# Sheet1.net
KiCad netlist of a schematic drawn in Altium Designer
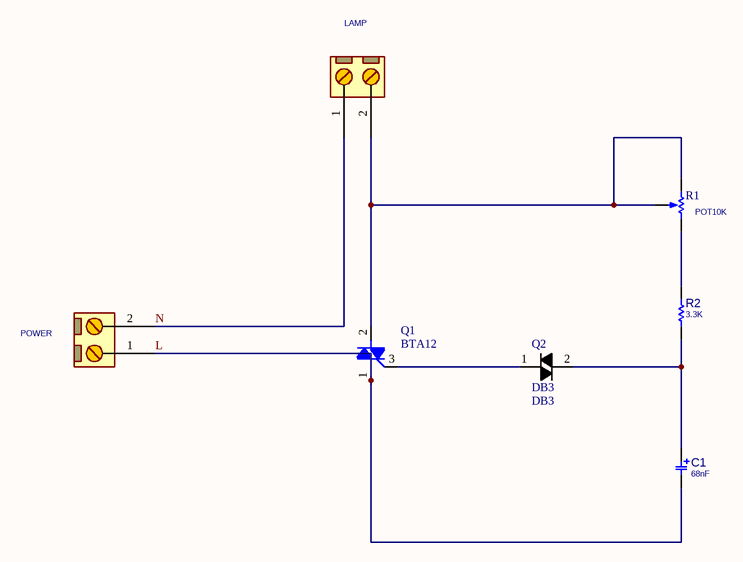
[diagram p0: Sheet1.SchDoc]

(export (version "E")
  (design (tool "Eeschema 10.0.6"))
  (components
    (comp (ref "C1")
      (value "68nF")
      (footprint "C_FLM_7X5H11")
      (description "CAP, THD, FILM,")
      (fields (field (name "MANF_P#") "MANF_PART#") (field (name "MANF") "MANF"))
      (libsource (lib "passive_thd") (part "CAP_THD_FLM"))
    )
    (comp (ref "LAMP")
      (value "CONN_TB2")
      (footprint "MSTB_2")
      (description "CONN, PHOENIX MSTB, 5-G, 5.08mm pitch")
      (libsource (lib "") (part "CONN_MSTB_2_1"))
    )
    (comp (ref "POWER")
      (value "CONN_TB2")
      (footprint "MSTB_2")
      (description "CONN, PHOENIX MSTB, 5-G, 5.08mm pitch")
      (libsource (lib "conn_terminalB") (part "CONN_MSTB_2"))
    )
    (comp (ref "Q1")
      (value "BTA12")
      (footprint "TO220_3")
      (description "Triac, 600V, 12A, TO-220")
      (fields (field (name "MANF_P#") "BTA12-600BW, BTA12-600CW, BTA12-600TW") (field (name "MANF") "ST"))
      (libsource (lib "triac_diac") (part "TRIAC_BTA12-600_TO220"))
    )
    (comp (ref "Q2")
      (value "DB3")
      (footprint "D_AX03_DO35")
      (description "Diac, 32VBO, DO-35")
      (fields (field (name "MANF") "ST") (field (name "ALTIUM_VALUE") "DB3"))
      (libsource (lib "triac_diac") (part "DIAC_DB3_DO35"))
    )
    (comp (ref "R1")
      (value "POT10K")
      (footprint "VOL_R")
      (description "RESISTOR, THD, Potentiometer Volume")
      (libsource (lib "resistor_pot_trimmer") (part "RES_THD_POT_VOL"))
    )
    (comp (ref "R2")
      (value "3.3K")
      (footprint "R025W_AX04")
      (description "RESISTOR, THD")
      (fields (field (name "MANF_P#") "RK73H1ETTP4701F") (field (name "MANF") "KOA SPEER"))
      (libsource (lib "passive_thd") (part "RES_THD"))
    )
  )
  (nets
    (net (code "1") (name "/L") (class "Default")
      (node (ref "C1") (pin "2") (pinfunction "2_2") (pintype "passive"))
      (node (ref "POWER") (pin "1") (pinfunction "1_1") (pintype "passive"))
      (node (ref "Q1") (pin "1") (pinfunction "T1_1") (pintype "passive"))
    )
    (net (code "2") (name "/N") (class "Default")
      (node (ref "LAMP") (pin "1") (pinfunction "1_1") (pintype "passive"))
      (node (ref "POWER") (pin "2") (pinfunction "2_2") (pintype "passive"))
    )
    (net (code "3") (name "Net-(Q1-G)") (class "Default")
      (node (ref "Q1") (pin "3") (pinfunction "G_3") (pintype "passive"))
      (node (ref "Q2") (pin "1") (pinfunction "A1_1") (pintype "passive"))
    )
    (net (code "4") (name "Net-(Q1-T2)") (class "Default")
      (node (ref "LAMP") (pin "2") (pinfunction "2_2") (pintype "passive"))
      (node (ref "Q1") (pin "2") (pinfunction "T2_2") (pintype "passive"))
      (node (ref "R1") (pin "1") (pinfunction "TOP_1") (pintype "passive"))
      (node (ref "R1") (pin "2") (pinfunction "TAP_2") (pintype "passive"))
    )
    (net (code "5") (name "Net-(Q2-A2)") (class "Default")
      (node (ref "C1") (pin "1") (pinfunction "1_1") (pintype "passive"))
      (node (ref "Q2") (pin "2") (pinfunction "A2_2") (pintype "passive"))
      (node (ref "R2") (pin "1") (pinfunction "1_1") (pintype "passive"))
    )
    (net (code "6") (name "Net-(R1-BOT)") (class "Default")
      (node (ref "R1") (pin "3") (pinfunction "BOT_3") (pintype "passive"))
      (node (ref "R2") (pin "2") (pinfunction "2_2") (pintype "passive"))
    )
  )
)
